# 01_-_MCU.net
KiCad netlist of a schematic drawn in Altium Designer
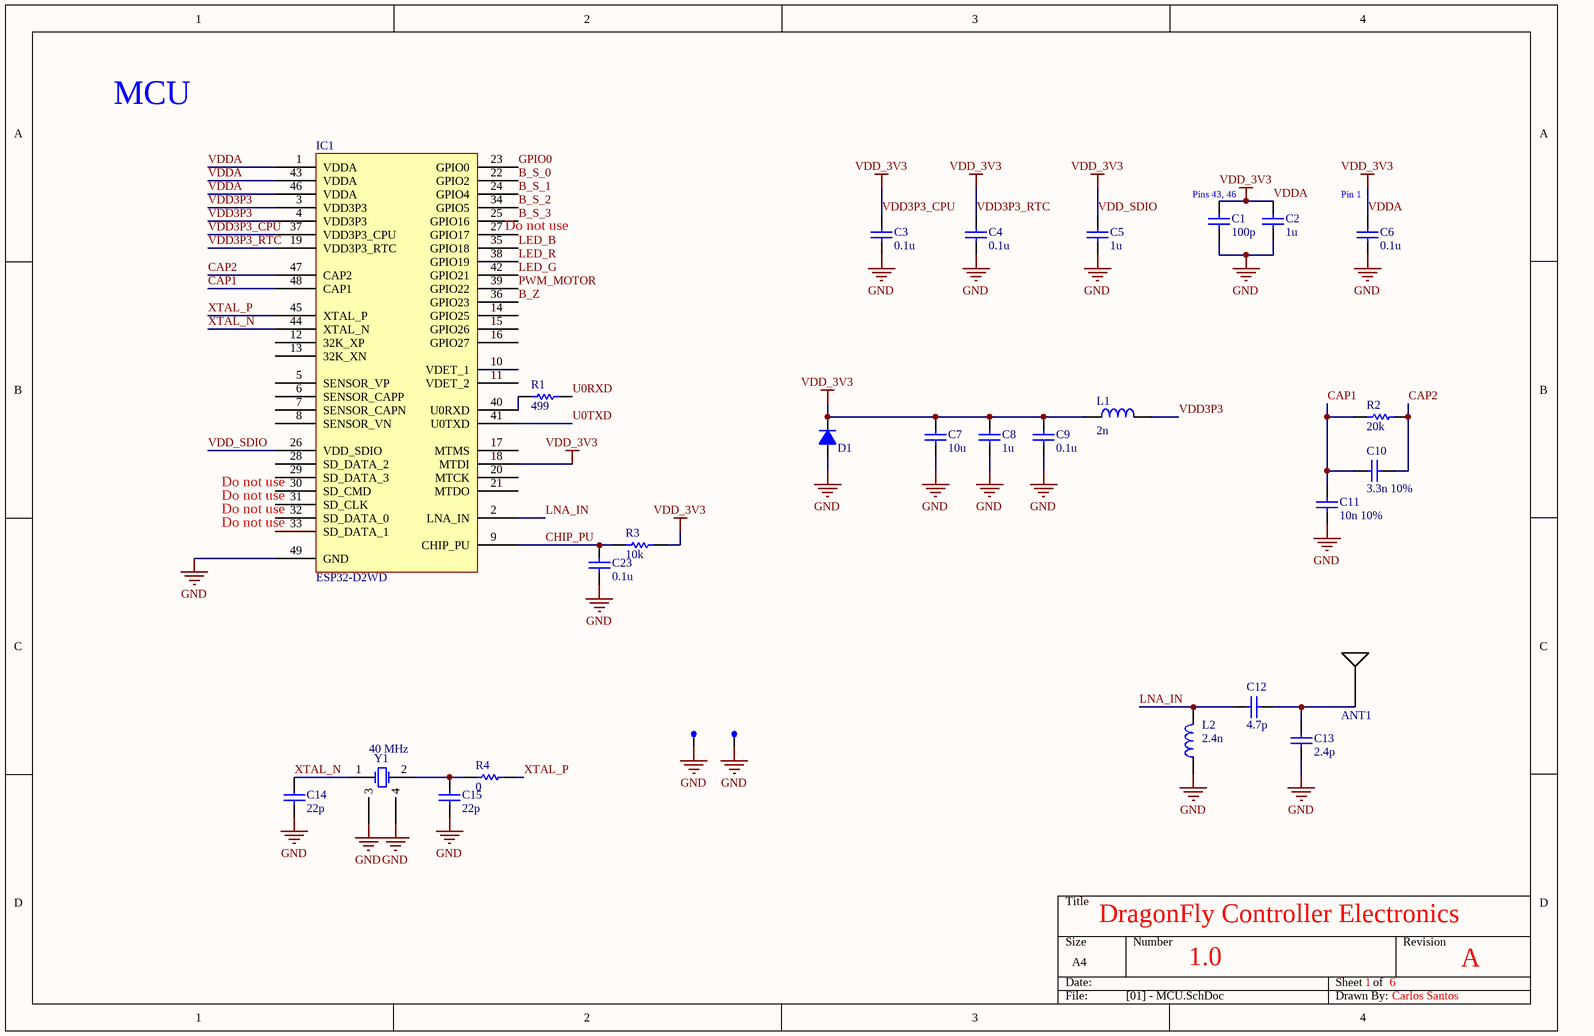
[diagram p0: [01] - MCU.SchDoc]

(export (version "E")
  (design (tool "Eeschema 10.0.6"))
  (components
    (comp (ref "ANT1")
      (value "2.4 GHz Ant")
      (footprint "2450AT18A100E")
      (description "2.4GHz Chip RF Antenna 2.4GHz")
      (libsource (lib "Mine") (part "2.4 GHz Ant"))
    )
    (comp (ref "C1")
      (value "100p")
      (footprint "0402 - Capacitor")
      (fields (field (name "Comment") "Capacitor"))
      (libsource (lib "Mine") (part "Capacitor"))
    )
    (comp (ref "C2")
      (value "1u")
      (footprint "0402 - Capacitor")
      (fields (field (name "Comment") "Capacitor"))
      (libsource (lib "Mine") (part "Capacitor"))
    )
    (comp (ref "C3")
      (value "0.1u")
      (footprint "0402 - Capacitor")
      (fields (field (name "Comment") "Capacitor"))
      (libsource (lib "Mine") (part "Capacitor"))
    )
    (comp (ref "C4")
      (value "0.1u")
      (footprint "0402 - Capacitor")
      (fields (field (name "Comment") "Capacitor"))
      (libsource (lib "Mine") (part "Capacitor"))
    )
    (comp (ref "C5")
      (value "1u")
      (footprint "0402 - Capacitor")
      (fields (field (name "Comment") "Capacitor"))
      (libsource (lib "Mine") (part "Capacitor"))
    )
    (comp (ref "C6")
      (value "0.1u")
      (footprint "0402 - Capacitor")
      (fields (field (name "Comment") "Capacitor"))
      (libsource (lib "Mine") (part "Capacitor"))
    )
    (comp (ref "C7")
      (value "10u")
      (footprint "0603 - Capacitor")
      (fields (field (name "Comment") "Capacitor"))
      (libsource (lib "Mine") (part "Capacitor"))
    )
    (comp (ref "C8")
      (value "1u")
      (footprint "0402 - Capacitor")
      (fields (field (name "Comment") "Capacitor"))
      (libsource (lib "Mine") (part "Capacitor"))
    )
    (comp (ref "C9")
      (value "0.1u")
      (footprint "0402 - Capacitor")
      (fields (field (name "Comment") "Capacitor"))
      (libsource (lib "Mine") (part "Capacitor"))
    )
    (comp (ref "C10")
      (value "3.3n 10%")
      (footprint "0402 - Capacitor")
      (fields (field (name "Comment") "Capacitor"))
      (libsource (lib "Mine") (part "Capacitor"))
    )
    (comp (ref "C11")
      (value "10n 10%")
      (footprint "0402 - Capacitor")
      (fields (field (name "Comment") "Capacitor"))
      (libsource (lib "Mine") (part "Capacitor"))
    )
    (comp (ref "C12")
      (value "4.7p")
      (footprint "0402 - Capacitor")
      (fields (field (name "Comment") "Capacitor"))
      (libsource (lib "Mine") (part "Capacitor"))
    )
    (comp (ref "C13")
      (value "2.4p")
      (footprint "0402 - Capacitor")
      (fields (field (name "Comment") "Capacitor"))
      (libsource (lib "Mine") (part "Capacitor"))
    )
    (comp (ref "C14")
      (value "22p")
      (footprint "0402 - Capacitor")
      (fields (field (name "Comment") "Capacitor"))
      (libsource (lib "Mine") (part "Capacitor"))
    )
    (comp (ref "C15")
      (value "22p")
      (footprint "0402 - Capacitor")
      (fields (field (name "Comment") "Capacitor"))
      (libsource (lib "Mine") (part "Capacitor"))
    )
    (comp (ref "C23")
      (value "0.1u")
      (footprint "0402 - Capacitor")
      (fields (field (name "Comment") "Capacitor"))
      (libsource (lib "Mine") (part "Capacitor"))
    )
    (comp (ref "D1")
      (value "Diode")
      (footprint "SOD 923")
      (fields (field (name "DIGIKEY PART #") "ESD9X5.0ST5GOSCT-ND"))
      (libsource (lib "Mine") (part "Diode"))
    )
    (comp (ref "IC1")
      (value "ESP32-D2WD")
      (footprint "ESP32 QFN35P500X500X90_HS-49N")
      (fields (field (name "DIGIKEY PART #") "1904-1005-1-ND"))
      (libsource (lib "Mine") (part "ESP32-D2WD"))
    )
    (comp (ref "L1")
      (value "2n")
      (footprint "0402 - inductor")
      (fields (field (name "Comment") "Inductor"))
      (libsource (lib "") (part "Inductor_1"))
    )
    (comp (ref "L2")
      (value "2.4n")
      (footprint "0402 - inductor")
      (fields (field (name "Comment") "Inductor"))
      (libsource (lib "Mine") (part "Inductor"))
    )
    (comp (ref "R1")
      (value "499")
      (footprint "0402 - Resistor")
      (fields (field (name "Comment") "Resistor"))
      (libsource (lib "Mine") (part "Resistor"))
    )
    (comp (ref "R2")
      (value "20k")
      (footprint "0402 - Resistor")
      (fields (field (name "Comment") "Resistor"))
      (libsource (lib "Mine") (part "Resistor"))
    )
    (comp (ref "R3")
      (value "10k")
      (footprint "0402 - Resistor")
      (fields (field (name "Comment") "Resistor"))
      (libsource (lib "Mine") (part "Resistor"))
    )
    (comp (ref "R4")
      (value "0")
      (footprint "0402 - Resistor")
      (fields (field (name "Comment") "Resistor"))
      (libsource (lib "Mine") (part "Resistor"))
    )
    (comp (ref "SP1")
      (value "Signal Point")
      (footprint "Signal_point_1mm")
      (libsource (lib "Mine") (part "Signal Point"))
    )
    (comp (ref "SP2")
      (value "Signal Point")
      (footprint "Signal_point_1mm")
      (libsource (lib "Mine") (part "Signal Point"))
    )
    (comp (ref "Y1")
      (value "40 MHz")
      (footprint "XTAL 1.6X1.2MM 4-SMD")
      (fields (field (name "DIGIKEY PART #") "535-13987-1-ND") (field (name "Comment") "XTAL_4"))
      (libsource (lib "Mine") (part "XTAL_4"))
    )
  )
  (nets
    (net (code "1") (name "/B_S_0") (class "Default")
      (node (ref "IC1") (pin "22") (pinfunction "GPIO2_22") (pintype "passive"))
    )
    (net (code "2") (name "/B_S_1") (class "Default")
      (node (ref "IC1") (pin "24") (pinfunction "GPIO4_24") (pintype "passive"))
    )
    (net (code "3") (name "/B_S_2") (class "Default")
      (node (ref "IC1") (pin "34") (pinfunction "GPIO5_34") (pintype "passive"))
    )
    (net (code "4") (name "/B_S_3") (class "Default")
      (node (ref "IC1") (pin "25") (pinfunction "GPIO16_25") (pintype "passive"))
    )
    (net (code "5") (name "/B_Z") (class "Default")
      (node (ref "IC1") (pin "36") (pinfunction "GPIO23_36") (pintype "passive"))
    )
    (net (code "6") (name "/CAP1") (class "Default")
      (node (ref "C10") (pin "2") (pinfunction "2_2") (pintype "passive"))
      (node (ref "C11") (pin "2") (pinfunction "2_2") (pintype "passive"))
      (node (ref "IC1") (pin "48") (pinfunction "CAP1_48") (pintype "passive"))
      (node (ref "R2") (pin "2") (pinfunction "2_2") (pintype "passive"))
    )
    (net (code "7") (name "/CAP2") (class "Default")
      (node (ref "C10") (pin "1") (pinfunction "1_1") (pintype "passive"))
      (node (ref "IC1") (pin "47") (pinfunction "CAP2_47") (pintype "passive"))
      (node (ref "R2") (pin "1") (pinfunction "1_1") (pintype "passive"))
    )
    (net (code "8") (name "/CHIP_PU") (class "Default")
      (node (ref "C23") (pin "2") (pinfunction "2_2") (pintype "passive"))
      (node (ref "IC1") (pin "9") (pinfunction "CHIP_PU_9") (pintype "passive"))
      (node (ref "R3") (pin "2") (pinfunction "2_2") (pintype "passive"))
    )
    (net (code "9") (name "/GPIO0") (class "Default")
      (node (ref "IC1") (pin "23") (pinfunction "GPIO0_23") (pintype "passive"))
    )
    (net (code "10") (name "/LED_B") (class "Default")
      (node (ref "IC1") (pin "35") (pinfunction "GPIO18_35") (pintype "passive"))
    )
    (net (code "11") (name "/LED_G") (class "Default")
      (node (ref "IC1") (pin "42") (pinfunction "GPIO21_42") (pintype "passive"))
    )
    (net (code "12") (name "/LED_R") (class "Default")
      (node (ref "IC1") (pin "38") (pinfunction "GPIO19_38") (pintype "passive"))
    )
    (net (code "13") (name "/LNA_IN") (class "Default")
      (node (ref "C12") (pin "2") (pinfunction "2_2") (pintype "passive"))
      (node (ref "IC1") (pin "2") (pinfunction "LNA_IN_2") (pintype "passive"))
      (node (ref "L2") (pin "2") (pinfunction "2_2") (pintype "passive"))
    )
    (net (code "14") (name "/PWM_MOTOR") (class "Default")
      (node (ref "IC1") (pin "39") (pinfunction "GPIO22_39") (pintype "passive"))
    )
    (net (code "15") (name "/U0RXD") (class "Default")
      (node (ref "R1") (pin "1") (pinfunction "1_1") (pintype "passive"))
    )
    (net (code "16") (name "/U0TXD") (class "Default")
      (node (ref "IC1") (pin "41") (pinfunction "U0TXD_41") (pintype "passive"))
    )
    (net (code "17") (name "/VDD3P3") (class "Default")
      (node (ref "IC1") (pin "3") (pinfunction "VDD3P3_3") (pintype "passive"))
      (node (ref "IC1") (pin "4") (pinfunction "VDD3P3_4") (pintype "passive"))
      (node (ref "L1") (pin "2") (pinfunction "2_2") (pintype "passive"))
    )
    (net (code "18") (name "/XTAL_N") (class "Default")
      (node (ref "C14") (pin "2") (pinfunction "2_2") (pintype "passive"))
      (node (ref "IC1") (pin "44") (pinfunction "XTAL_N_44") (pintype "passive"))
      (node (ref "Y1") (pin "1") (pinfunction "OSC1_1") (pintype "passive"))
    )
    (net (code "19") (name "/XTAL_P") (class "Default")
      (node (ref "IC1") (pin "45") (pinfunction "XTAL_P_45") (pintype "passive"))
      (node (ref "R4") (pin "1") (pinfunction "1_1") (pintype "passive"))
    )
    (net (code "20") (name "GND") (class "Default")
      (node (ref "C1") (pin "1") (pinfunction "1_1") (pintype "passive"))
      (node (ref "C11") (pin "1") (pinfunction "1_1") (pintype "passive"))
      (node (ref "C13") (pin "1") (pinfunction "1_1") (pintype "passive"))
      (node (ref "C14") (pin "1") (pinfunction "1_1") (pintype "passive"))
      (node (ref "C15") (pin "1") (pinfunction "1_1") (pintype "passive"))
      (node (ref "C2") (pin "1") (pinfunction "1_1") (pintype "passive"))
      (node (ref "C23") (pin "1") (pinfunction "1_1") (pintype "passive"))
      (node (ref "C3") (pin "1") (pinfunction "1_1") (pintype "passive"))
      (node (ref "C4") (pin "1") (pinfunction "1_1") (pintype "passive"))
      (node (ref "C5") (pin "1") (pinfunction "1_1") (pintype "passive"))
      (node (ref "C6") (pin "1") (pinfunction "1_1") (pintype "passive"))
      (node (ref "C7") (pin "1") (pinfunction "1_1") (pintype "passive"))
      (node (ref "C8") (pin "1") (pinfunction "1_1") (pintype "passive"))
      (node (ref "C9") (pin "1") (pinfunction "1_1") (pintype "passive"))
      (node (ref "D1") (pin "1") (pinfunction "A_1") (pintype "passive"))
      (node (ref "IC1") (pin "49") (pinfunction "GND_49") (pintype "passive"))
      (node (ref "L2") (pin "1") (pinfunction "1_1") (pintype "passive"))
      (node (ref "SP1") (pin "0") (pinfunction "VIN_0") (pintype "passive"))
      (node (ref "SP2") (pin "0") (pinfunction "VIN_0") (pintype "passive"))
      (node (ref "Y1") (pin "3") (pinfunction "3_3") (pintype "passive"))
      (node (ref "Y1") (pin "4") (pinfunction "4_4") (pintype "passive"))
    )
    (net (code "21") (name "Net-(ANT1-Pad1)") (class "Default")
      (node (ref "ANT1") (pin "1") (pinfunction "1_1") (pintype "passive"))
      (node (ref "C12") (pin "1") (pinfunction "1_1") (pintype "passive"))
      (node (ref "C13") (pin "2") (pinfunction "2_2") (pintype "passive"))
    )
    (net (code "22") (name "Net-(IC1-U0RXD)") (class "Default")
      (node (ref "IC1") (pin "40") (pinfunction "U0RXD_40") (pintype "passive"))
      (node (ref "R1") (pin "2") (pinfunction "2_2") (pintype "passive"))
    )
    (net (code "23") (name "Net-(Y1-OSC2)") (class "Default")
      (node (ref "C15") (pin "2") (pinfunction "2_2") (pintype "passive"))
      (node (ref "R4") (pin "2") (pinfunction "2_2") (pintype "passive"))
      (node (ref "Y1") (pin "2") (pinfunction "OSC2_2") (pintype "passive"))
    )
    (net (code "24") (name "VDD_3V3") (class "Default")
      (node (ref "C1") (pin "2") (pinfunction "2_2") (pintype "passive"))
      (node (ref "C2") (pin "2") (pinfunction "2_2") (pintype "passive"))
      (node (ref "C3") (pin "2") (pinfunction "2_2") (pintype "passive"))
      (node (ref "C4") (pin "2") (pinfunction "2_2") (pintype "passive"))
      (node (ref "C5") (pin "2") (pinfunction "2_2") (pintype "passive"))
      (node (ref "C6") (pin "2") (pinfunction "2_2") (pintype "passive"))
      (node (ref "C7") (pin "2") (pinfunction "2_2") (pintype "passive"))
      (node (ref "C8") (pin "2") (pinfunction "2_2") (pintype "passive"))
      (node (ref "C9") (pin "2") (pinfunction "2_2") (pintype "passive"))
      (node (ref "D1") (pin "2") (pinfunction "K_2") (pintype "passive"))
      (node (ref "IC1") (pin "1") (pinfunction "VDDA_1") (pintype "passive"))
      (node (ref "IC1") (pin "18") (pinfunction "MTDI_18") (pintype "passive"))
      (node (ref "IC1") (pin "19") (pinfunction "VDD3P3_RTC_19") (pintype "passive"))
      (node (ref "IC1") (pin "26") (pinfunction "VDD_SDIO_26") (pintype "passive"))
      (node (ref "IC1") (pin "37") (pinfunction "VDD3P3_CPU_37") (pintype "passive"))
      (node (ref "IC1") (pin "43") (pinfunction "VDDA_43") (pintype "passive"))
      (node (ref "IC1") (pin "46") (pinfunction "VDDA_46") (pintype "passive"))
      (node (ref "L1") (pin "1") (pinfunction "1_1") (pintype "passive"))
      (node (ref "R3") (pin "1") (pinfunction "1_1") (pintype "passive"))
    )
    (net (code "25") (name "unconnected-(IC1-32K_XN-Pad13)") (class "Default")
      (node (ref "IC1") (pin "13") (pinfunction "32K_XN_13") (pintype "passive"))
    )
    (net (code "26") (name "unconnected-(IC1-32K_XP-Pad12)") (class "Default")
      (node (ref "IC1") (pin "12") (pinfunction "32K_XP_12") (pintype "passive"))
    )
    (net (code "27") (name "unconnected-(IC1-GPIO17-Pad27)") (class "Default")
      (node (ref "IC1") (pin "27") (pinfunction "GPIO17_27") (pintype "passive"))
    )
    (net (code "28") (name "unconnected-(IC1-GPIO25-Pad14)") (class "Default")
      (node (ref "IC1") (pin "14") (pinfunction "GPIO25_14") (pintype "passive"))
    )
    (net (code "29") (name "unconnected-(IC1-GPIO26-Pad15)") (class "Default")
      (node (ref "IC1") (pin "15") (pinfunction "GPIO26_15") (pintype "passive"))
    )
    (net (code "30") (name "unconnected-(IC1-GPIO27-Pad16)") (class "Default")
      (node (ref "IC1") (pin "16") (pinfunction "GPIO27_16") (pintype "passive"))
    )
    (net (code "31") (name "unconnected-(IC1-MTCK-Pad20)") (class "Default")
      (node (ref "IC1") (pin "20") (pinfunction "MTCK_20") (pintype "passive"))
    )
    (net (code "32") (name "unconnected-(IC1-MTDO-Pad21)") (class "Default")
      (node (ref "IC1") (pin "21") (pinfunction "MTDO_21") (pintype "passive"))
    )
    (net (code "33") (name "unconnected-(IC1-MTMS-Pad17)") (class "Default")
      (node (ref "IC1") (pin "17") (pinfunction "MTMS_17") (pintype "passive"))
    )
    (net (code "34") (name "unconnected-(IC1-SD_CLK-Pad31)") (class "Default")
      (node (ref "IC1") (pin "31") (pinfunction "SD_CLK_31") (pintype "passive"))
    )
    (net (code "35") (name "unconnected-(IC1-SD_CMD-Pad30)") (class "Default")
      (node (ref "IC1") (pin "30") (pinfunction "SD_CMD_30") (pintype "passive"))
    )
    (net (code "36") (name "unconnected-(IC1-SD_DATA_0-Pad32)") (class "Default")
      (node (ref "IC1") (pin "32") (pinfunction "SD_DATA_0_32") (pintype "passive"))
    )
    (net (code "37") (name "unconnected-(IC1-SD_DATA_1-Pad33)") (class "Default")
      (node (ref "IC1") (pin "33") (pinfunction "SD_DATA_1_33") (pintype "passive"))
    )
    (net (code "38") (name "unconnected-(IC1-SD_DATA_2-Pad28)") (class "Default")
      (node (ref "IC1") (pin "28") (pinfunction "SD_DATA_2_28") (pintype "passive"))
    )
    (net (code "39") (name "unconnected-(IC1-SD_DATA_3-Pad29)") (class "Default")
      (node (ref "IC1") (pin "29") (pinfunction "SD_DATA_3_29") (pintype "passive"))
    )
    (net (code "40") (name "unconnected-(IC1-SENSOR_CAPN-Pad7)") (class "Default")
      (node (ref "IC1") (pin "7") (pinfunction "SENSOR_CAPN_7") (pintype "passive"))
    )
    (net (code "41") (name "unconnected-(IC1-SENSOR_CAPP-Pad6)") (class "Default")
      (node (ref "IC1") (pin "6") (pinfunction "SENSOR_CAPP_6") (pintype "passive"))
    )
    (net (code "42") (name "unconnected-(IC1-SENSOR_VN-Pad8)") (class "Default")
      (node (ref "IC1") (pin "8") (pinfunction "SENSOR_VN_8") (pintype "passive"))
    )
    (net (code "43") (name "unconnected-(IC1-SENSOR_VP-Pad5)") (class "Default")
      (node (ref "IC1") (pin "5") (pinfunction "SENSOR_VP_5") (pintype "passive"))
    )
    (net (code "44") (name "unconnected-(IC1-VDET_1-Pad10)") (class "Default")
      (node (ref "IC1") (pin "10") (pinfunction "VDET_1_10") (pintype "passive"))
    )
    (net (code "45") (name "unconnected-(IC1-VDET_2-Pad11)") (class "Default")
      (node (ref "IC1") (pin "11") (pinfunction "VDET_2_11") (pintype "passive"))
    )
  )
)
